# MSSRP-HUMID_TEMP_SENSE.net
KiCad netlist of a schematic drawn in EAGLE
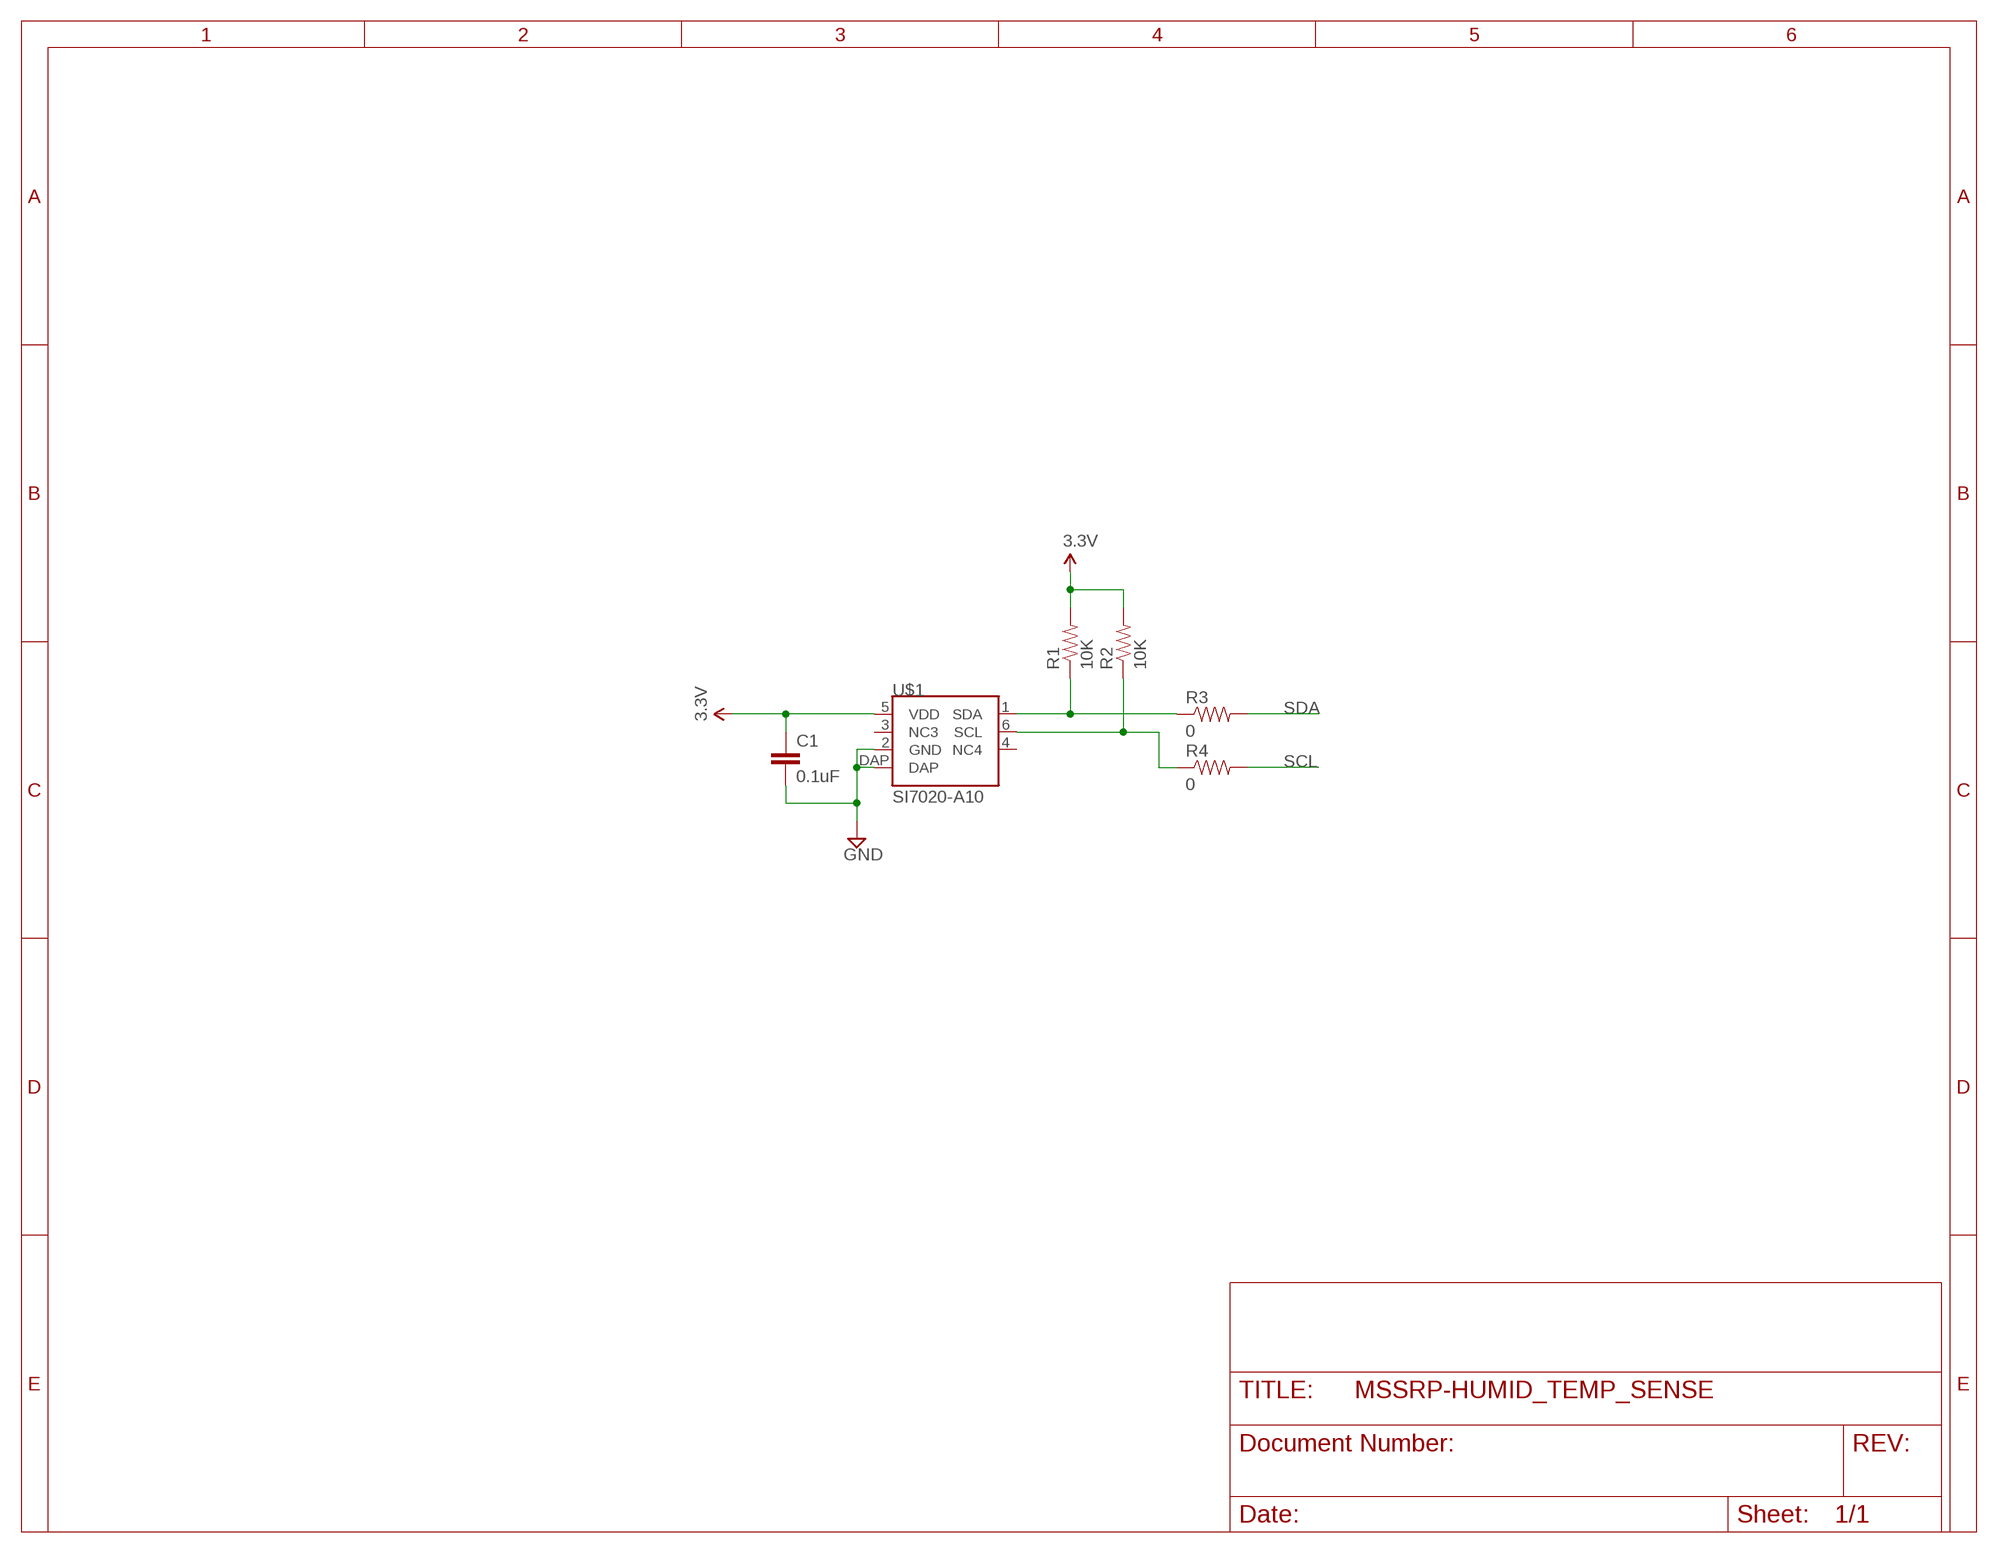
[diagram p0: schematic, sheet 1]

(export (version "E")
  (design (tool "Eeschema 10.0.6"))
  (components
    (comp (ref "C1")
      (value "0.1uF")
      (footprint "eagle-import:0603-CAP")
      (libsource (lib "eagle-import") (part "0.1UF-25V-5%(0603)"))
    )
    (comp (ref "R1")
      (value "10K")
      (footprint "eagle-import:0603-RES")
      (libsource (lib "eagle-import") (part "10KOHM1/10W1%(0603)0603"))
    )
    (comp (ref "R2")
      (value "10K")
      (footprint "eagle-import:0603-RES")
      (libsource (lib "eagle-import") (part "10KOHM1/10W1%(0603)0603"))
    )
    (comp (ref "R3")
      (value "0")
      (footprint "eagle-import:0603")
      (libsource (lib "eagle-import") (part "0OHM1/10W5%(0603)"))
    )
    (comp (ref "R4")
      (value "0")
      (footprint "eagle-import:0603")
      (libsource (lib "eagle-import") (part "0OHM1/10W5%(0603)"))
    )
    (comp (ref "U$1")
      (value "SI7020-A10")
      (footprint "eagle-import:DFN6")
      (libsource (lib "eagle-import") (part "SI7020-A10"))
    )
  )
  (nets
    (net (code "1") (name "/SCL") (class "Default")
      (node (ref "R4") (pin "2") (pinfunction "2_2") (pintype "passive"))
    )
    (net (code "2") (name "/SDA") (class "Default")
      (node (ref "R3") (pin "2") (pinfunction "2_2") (pintype "passive"))
    )
    (net (code "3") (name "3.3V") (class "Default")
      (node (ref "C1") (pin "1") (pinfunction "1_1") (pintype "passive"))
      (node (ref "R1") (pin "2") (pinfunction "2_2") (pintype "passive"))
      (node (ref "R2") (pin "2") (pinfunction "2_2") (pintype "passive"))
      (node (ref "U$1") (pin "5") (pinfunction "VDD_5") (pintype "power_in"))
    )
    (net (code "4") (name "GND") (class "Default")
      (node (ref "C1") (pin "2") (pinfunction "2_2") (pintype "passive"))
      (node (ref "U$1") (pin "2") (pinfunction "GND_2") (pintype "power_in"))
      (node (ref "U$1") (pin "DAP") (pinfunction "DAP_DAP") (pintype "bidirectional"))
    )
    (net (code "5") (name "Net-(U$1-SCL)") (class "Default")
      (node (ref "R2") (pin "1") (pinfunction "1_1") (pintype "passive"))
      (node (ref "R4") (pin "1") (pinfunction "1_1") (pintype "passive"))
      (node (ref "U$1") (pin "6") (pinfunction "SCL_6") (pintype "bidirectional"))
    )
    (net (code "6") (name "Net-(U$1-SDA)") (class "Default")
      (node (ref "R1") (pin "1") (pinfunction "1_1") (pintype "passive"))
      (node (ref "R3") (pin "1") (pinfunction "1_1") (pintype "passive"))
      (node (ref "U$1") (pin "1") (pinfunction "SDA_1") (pintype "bidirectional"))
    )
    (net (code "7") (name "unconnected-(U$1-NC3-Pad3)") (class "Default")
      (node (ref "U$1") (pin "3") (pinfunction "NC3_3") (pintype "no_connect"))
    )
    (net (code "8") (name "unconnected-(U$1-NC4-Pad4)") (class "Default")
      (node (ref "U$1") (pin "4") (pinfunction "NC4_4") (pintype "no_connect"))
    )
  )
)
